# main.net
KiCad netlist of a schematic drawn in EAGLE
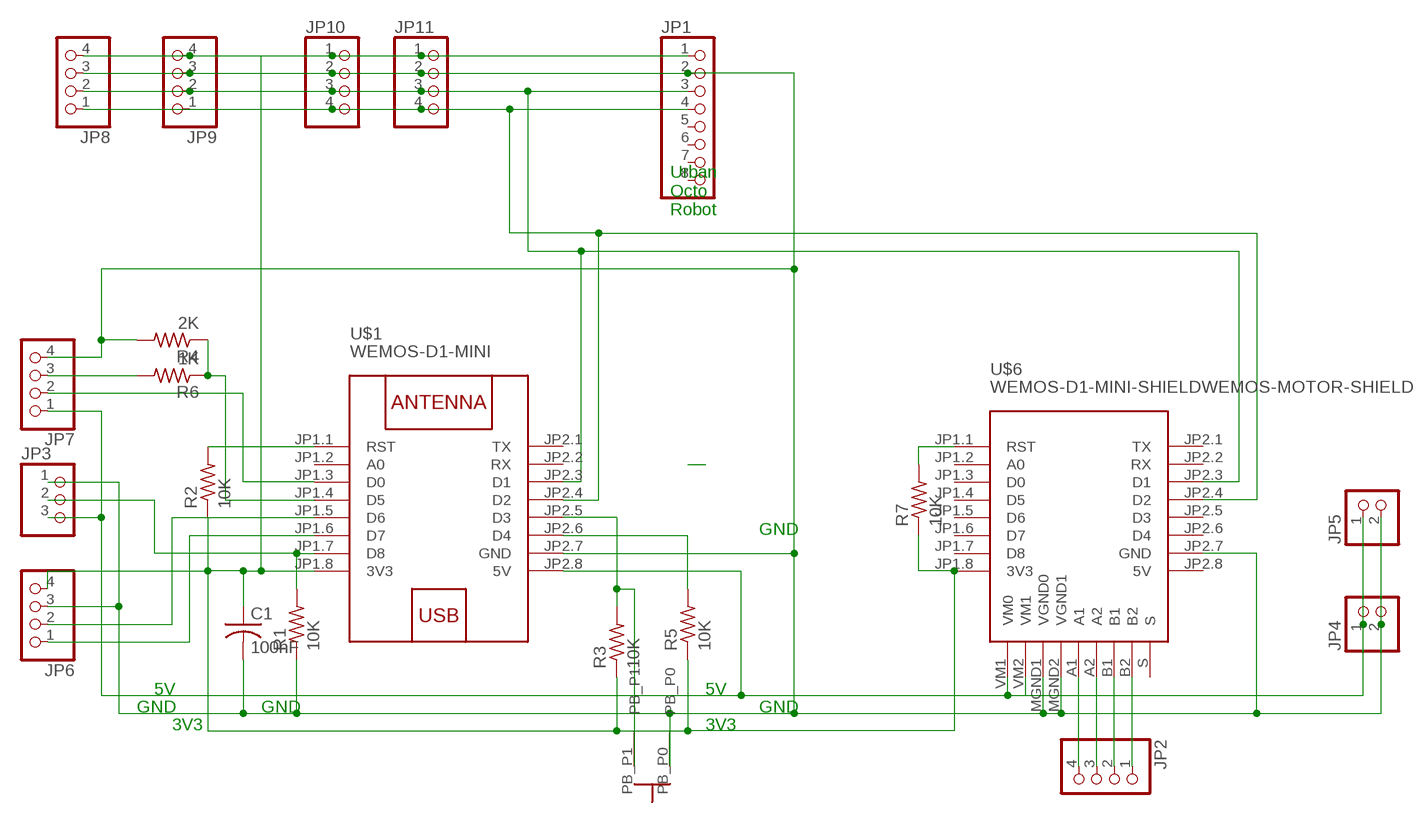
[diagram p0: schematic, sheet 1]

(export (version "E")
  (design (tool "Eeschema 10.0.6"))
  (components
    (comp (ref "C1")
      (value "100nF")
      (footprint "eagle-import:C050-024X044")
      (libsource (lib "eagle-import") (part "C-US050-024X044"))
    )
    (comp (ref "JP1")
      (value "PINHD-1X8")
      (footprint "eagle-import:1X08")
      (libsource (lib "eagle-import") (part "PINHD-1X8"))
    )
    (comp (ref "JP2")
      (value "PINHD-1X4/90")
      (footprint "eagle-import:1X04_90")
      (libsource (lib "eagle-import") (part "PINHD-1X4/90"))
    )
    (comp (ref "JP3")
      (value "PINHD-1X3")
      (footprint "eagle-import:1X03")
      (libsource (lib "eagle-import") (part "PINHD-1X3"))
    )
    (comp (ref "JP4")
      (value "PINHD-1X2")
      (footprint "eagle-import:1X02")
      (libsource (lib "eagle-import") (part "PINHD-1X2"))
    )
    (comp (ref "JP5")
      (value "PINHD-1X2")
      (footprint "eagle-import:1X02")
      (libsource (lib "eagle-import") (part "PINHD-1X2"))
    )
    (comp (ref "JP6")
      (value "PINHD-1X4")
      (footprint "eagle-import:1X04")
      (libsource (lib "eagle-import") (part "PINHD-1X4"))
    )
    (comp (ref "JP7")
      (value "PINHD-1X4")
      (footprint "eagle-import:1X04")
      (libsource (lib "eagle-import") (part "PINHD-1X4"))
    )
    (comp (ref "JP8")
      (value "PINHD-1X4")
      (footprint "eagle-import:1X04")
      (libsource (lib "eagle-import") (part "PINHD-1X4"))
    )
    (comp (ref "JP9")
      (value "PINHD-1X4")
      (footprint "eagle-import:1X04")
      (libsource (lib "eagle-import") (part "PINHD-1X4"))
    )
    (comp (ref "JP10")
      (value "PINHD-1X4")
      (footprint "eagle-import:1X04")
      (libsource (lib "eagle-import") (part "PINHD-1X4"))
    )
    (comp (ref "JP11")
      (value "PINHD-1X4")
      (footprint "eagle-import:1X04")
      (libsource (lib "eagle-import") (part "PINHD-1X4"))
    )
    (comp (ref "R1")
      (value "10K")
      (footprint "eagle-import:0204_7")
      (libsource (lib "eagle-import") (part "R-US_0204/7"))
    )
    (comp (ref "R2")
      (value "10K")
      (footprint "eagle-import:0204_7")
      (libsource (lib "eagle-import") (part "R-US_0204/7"))
    )
    (comp (ref "R3")
      (value "10K")
      (footprint "eagle-import:0204_7")
      (libsource (lib "eagle-import") (part "R-US_0204/7"))
    )
    (comp (ref "R4")
      (value "2K")
      (footprint "eagle-import:0309V")
      (libsource (lib "eagle-import") (part "R-US_0309/V"))
    )
    (comp (ref "R5")
      (value "10K")
      (footprint "eagle-import:0204_7")
      (libsource (lib "eagle-import") (part "R-US_0204/7"))
    )
    (comp (ref "R6")
      (value "1K")
      (footprint "eagle-import:0309V")
      (libsource (lib "eagle-import") (part "R-US_0309/V"))
    )
    (comp (ref "R7")
      (value "10K")
      (footprint "eagle-import:0204_7")
      (libsource (lib "eagle-import") (part "R-US_0204/7"))
    )
    (comp (ref "U$1")
      (value "WEMOS-D1-MINI")
      (footprint "eagle-import:WEMOS-D1-MINI")
      (libsource (lib "eagle-import") (part "WEMOS-D1-MINI"))
    )
    (comp (ref "U$6")
      (value "WEMOS-D1-MINI-SHIELDWEMOS-MOTOR-SHIELD")
      (footprint "eagle-import:WEMOS-D1-MINI-SHIELD")
      (libsource (lib "eagle-import") (part "WEMOS-D1-MINI-SHIELDWEMOS-MOTOR-SHIELD"))
    )
    (comp (ref "U$7")
      (value "BUTTON6X6X10MMSIDE")
      (footprint "eagle-import:BUTTON6X6X10MMSIDE")
      (libsource (lib "eagle-import") (part "BUTTON6X6X10MMSIDE"))
    )
  )
  (nets
    (net (code "1") (name "/5V") (class "Default")
      (node (ref "U$6") (pin "JP2.8") (pinfunction "5V_JP2.8") (pintype "power_in"))
    )
    (net (code "2") (name "Net-(JP2-Pad1)") (class "Default")
      (node (ref "JP2") (pin "1") (pinfunction "1_1") (pintype "passive"))
      (node (ref "U$6") (pin "B2") (pinfunction "B2_B2") (pintype "bidirectional"))
    )
    (net (code "3") (name "Net-(JP2-Pad2)") (class "Default")
      (node (ref "JP2") (pin "2") (pinfunction "2_2") (pintype "passive"))
      (node (ref "U$6") (pin "B1") (pinfunction "B1_B1") (pintype "bidirectional"))
    )
    (net (code "4") (name "Net-(JP2-Pad3)") (class "Default")
      (node (ref "JP2") (pin "3") (pinfunction "3_3") (pintype "passive"))
      (node (ref "U$6") (pin "A2") (pinfunction "A2_A2") (pintype "bidirectional"))
    )
    (net (code "5") (name "Net-(JP2-Pad4)") (class "Default")
      (node (ref "JP2") (pin "4") (pinfunction "4_4") (pintype "passive"))
      (node (ref "U$6") (pin "A1") (pinfunction "A1_A1") (pintype "bidirectional"))
    )
    (net (code "6") (name "Net-(JP7-Pad3)") (class "Default")
      (node (ref "JP7") (pin "3") (pinfunction "3_3") (pintype "passive"))
      (node (ref "R6") (pin "2") (pinfunction "2_2") (pintype "passive"))
    )
    (net (code "7") (name "Net-(U$1-3V3)") (class "Default")
      (node (ref "C1") (pin "1") (pinfunction "1_1") (pintype "passive"))
      (node (ref "JP1") (pin "1") (pinfunction "1_1") (pintype "passive"))
      (node (ref "JP10") (pin "1") (pinfunction "1_1") (pintype "passive"))
      (node (ref "JP11") (pin "1") (pinfunction "1_1") (pintype "passive"))
      (node (ref "JP6") (pin "4") (pinfunction "4_4") (pintype "passive"))
      (node (ref "JP8") (pin "4") (pinfunction "4_4") (pintype "passive"))
      (node (ref "JP9") (pin "4") (pinfunction "4_4") (pintype "passive"))
      (node (ref "R2") (pin "1") (pinfunction "1_1") (pintype "passive"))
      (node (ref "R3") (pin "1") (pinfunction "1_1") (pintype "passive"))
      (node (ref "R5") (pin "1") (pinfunction "1_1") (pintype "passive"))
      (node (ref "R7") (pin "1") (pinfunction "1_1") (pintype "passive"))
      (node (ref "U$1") (pin "JP1.8") (pinfunction "3V3_JP1.8") (pintype "power_in"))
      (node (ref "U$6") (pin "JP1.8") (pinfunction "3V3_JP1.8") (pintype "power_in"))
    )
    (net (code "8") (name "Net-(U$1-5V)") (class "Default")
      (node (ref "JP3") (pin "3") (pinfunction "3_3") (pintype "passive"))
      (node (ref "JP4") (pin "1") (pinfunction "1_1") (pintype "passive"))
      (node (ref "JP5") (pin "1") (pinfunction "1_1") (pintype "passive"))
      (node (ref "JP7") (pin "1") (pinfunction "1_1") (pintype "passive"))
      (node (ref "U$1") (pin "JP2.8") (pinfunction "5V_JP2.8") (pintype "power_in"))
      (node (ref "U$6") (pin "VM1") (pinfunction "VM0_VM1") (pintype "bidirectional"))
      (node (ref "U$6") (pin "VM2") (pinfunction "VM1_VM2") (pintype "bidirectional"))
    )
    (net (code "9") (name "Net-(U$1-D0)") (class "Default")
      (node (ref "JP7") (pin "2") (pinfunction "2_2") (pintype "passive"))
      (node (ref "U$1") (pin "JP1.3") (pinfunction "D0_JP1.3") (pintype "bidirectional"))
    )
    (net (code "10") (name "Net-(U$1-D1)") (class "Default")
      (node (ref "JP1") (pin "3") (pinfunction "3_3") (pintype "passive"))
      (node (ref "JP10") (pin "3") (pinfunction "3_3") (pintype "passive"))
      (node (ref "JP11") (pin "3") (pinfunction "3_3") (pintype "passive"))
      (node (ref "JP8") (pin "2") (pinfunction "2_2") (pintype "passive"))
      (node (ref "JP9") (pin "2") (pinfunction "2_2") (pintype "passive"))
      (node (ref "U$1") (pin "JP2.3") (pinfunction "D1_JP2.3") (pintype "bidirectional"))
      (node (ref "U$6") (pin "JP2.3") (pinfunction "D1_JP2.3") (pintype "bidirectional"))
    )
    (net (code "11") (name "Net-(U$1-D2)") (class "Default")
      (node (ref "JP1") (pin "4") (pinfunction "4_4") (pintype "passive"))
      (node (ref "JP10") (pin "4") (pinfunction "4_4") (pintype "passive"))
      (node (ref "JP11") (pin "4") (pinfunction "4_4") (pintype "passive"))
      (node (ref "JP8") (pin "1") (pinfunction "1_1") (pintype "passive"))
      (node (ref "JP9") (pin "1") (pinfunction "1_1") (pintype "passive"))
      (node (ref "U$1") (pin "JP2.4") (pinfunction "D2_JP2.4") (pintype "bidirectional"))
      (node (ref "U$6") (pin "JP2.4") (pinfunction "D2_JP2.4") (pintype "bidirectional"))
    )
    (net (code "12") (name "Net-(U$1-D3)") (class "Default")
      (node (ref "R3") (pin "2") (pinfunction "2_2") (pintype "passive"))
      (node (ref "U$1") (pin "JP2.5") (pinfunction "D3_JP2.5") (pintype "bidirectional"))
      (node (ref "U$7") (pin "PB_P1") (pinfunction "PB_P1_PB_P1") (pintype "bidirectional"))
    )
    (net (code "13") (name "Net-(U$1-D4)") (class "Default")
      (node (ref "R5") (pin "2") (pinfunction "2_2") (pintype "passive"))
      (node (ref "U$1") (pin "JP2.6") (pinfunction "D4_JP2.6") (pintype "bidirectional"))
    )
    (net (code "14") (name "Net-(U$1-D5)") (class "Default")
      (node (ref "R4") (pin "1") (pinfunction "1_1") (pintype "passive"))
      (node (ref "R6") (pin "1") (pinfunction "1_1") (pintype "passive"))
      (node (ref "U$1") (pin "JP1.4") (pinfunction "D5_JP1.4") (pintype "bidirectional"))
    )
    (net (code "15") (name "Net-(U$1-D6)") (class "Default")
      (node (ref "JP6") (pin "2") (pinfunction "2_2") (pintype "passive"))
      (node (ref "U$1") (pin "JP1.5") (pinfunction "D6_JP1.5") (pintype "bidirectional"))
    )
    (net (code "16") (name "Net-(U$1-D7)") (class "Default")
      (node (ref "JP6") (pin "1") (pinfunction "1_1") (pintype "passive"))
      (node (ref "U$1") (pin "JP1.6") (pinfunction "D7_JP1.6") (pintype "bidirectional"))
    )
    (net (code "17") (name "Net-(U$1-D8)") (class "Default")
      (node (ref "JP3") (pin "2") (pinfunction "2_2") (pintype "passive"))
      (node (ref "R1") (pin "2") (pinfunction "2_2") (pintype "passive"))
      (node (ref "U$1") (pin "JP1.7") (pinfunction "D8_JP1.7") (pintype "bidirectional"))
    )
    (net (code "18") (name "Net-(U$1-GND)") (class "Default")
      (node (ref "C1") (pin "2") (pinfunction "2_2") (pintype "passive"))
      (node (ref "JP1") (pin "2") (pinfunction "2_2") (pintype "passive"))
      (node (ref "JP10") (pin "2") (pinfunction "2_2") (pintype "passive"))
      (node (ref "JP11") (pin "2") (pinfunction "2_2") (pintype "passive"))
      (node (ref "JP3") (pin "1") (pinfunction "1_1") (pintype "passive"))
      (node (ref "JP4") (pin "2") (pinfunction "2_2") (pintype "passive"))
      (node (ref "JP5") (pin "2") (pinfunction "2_2") (pintype "passive"))
      (node (ref "JP6") (pin "3") (pinfunction "3_3") (pintype "passive"))
      (node (ref "JP7") (pin "4") (pinfunction "4_4") (pintype "passive"))
      (node (ref "JP8") (pin "3") (pinfunction "3_3") (pintype "passive"))
      (node (ref "JP9") (pin "3") (pinfunction "3_3") (pintype "passive"))
      (node (ref "R1") (pin "1") (pinfunction "1_1") (pintype "passive"))
      (node (ref "R4") (pin "2") (pinfunction "2_2") (pintype "passive"))
      (node (ref "U$1") (pin "JP2.7") (pinfunction "GND_JP2.7") (pintype "power_in"))
      (node (ref "U$6") (pin "JP2.7") (pinfunction "GND_JP2.7") (pintype "power_in"))
      (node (ref "U$6") (pin "MGND1") (pinfunction "VGND0_MGND1") (pintype "bidirectional"))
      (node (ref "U$6") (pin "MGND2") (pinfunction "VGND1_MGND2") (pintype "bidirectional"))
      (node (ref "U$7") (pin "PB_P0") (pinfunction "PB_P0_PB_P0") (pintype "bidirectional"))
    )
    (net (code "19") (name "Net-(U$1-RST)") (class "Default")
      (node (ref "R2") (pin "2") (pinfunction "2_2") (pintype "passive"))
      (node (ref "U$1") (pin "JP1.1") (pinfunction "RST_JP1.1") (pintype "bidirectional"))
    )
    (net (code "20") (name "Net-(U$6-RST)") (class "Default")
      (node (ref "R7") (pin "2") (pinfunction "2_2") (pintype "passive"))
      (node (ref "U$6") (pin "JP1.1") (pinfunction "RST_JP1.1") (pintype "bidirectional"))
    )
    (net (code "21") (name "unconnected-(JP1-Pad5)") (class "Default")
      (node (ref "JP1") (pin "5") (pinfunction "5_5") (pintype "passive"))
    )
    (net (code "22") (name "unconnected-(JP1-Pad6)") (class "Default")
      (node (ref "JP1") (pin "6") (pinfunction "6_6") (pintype "passive"))
    )
    (net (code "23") (name "unconnected-(JP1-Pad7)") (class "Default")
      (node (ref "JP1") (pin "7") (pinfunction "7_7") (pintype "passive"))
    )
    (net (code "24") (name "unconnected-(JP1-Pad8)") (class "Default")
      (node (ref "JP1") (pin "8") (pinfunction "8_8") (pintype "passive"))
    )
    (net (code "25") (name "unconnected-(U$1-A0-PadJP1.2)") (class "Default")
      (node (ref "U$1") (pin "JP1.2") (pinfunction "A0_JP1.2") (pintype "bidirectional"))
    )
    (net (code "26") (name "unconnected-(U$1-RX-PadJP2.2)") (class "Default")
      (node (ref "U$1") (pin "JP2.2") (pinfunction "RX_JP2.2") (pintype "bidirectional"))
    )
    (net (code "27") (name "unconnected-(U$1-TX-PadJP2.1)") (class "Default")
      (node (ref "U$1") (pin "JP2.1") (pinfunction "TX_JP2.1") (pintype "bidirectional"))
    )
    (net (code "28") (name "unconnected-(U$6-A0-PadJP1.2)") (class "Default")
      (node (ref "U$6") (pin "JP1.2") (pinfunction "A0_JP1.2") (pintype "bidirectional"))
    )
    (net (code "29") (name "unconnected-(U$6-D0-PadJP1.3)") (class "Default")
      (node (ref "U$6") (pin "JP1.3") (pinfunction "D0_JP1.3") (pintype "bidirectional"))
    )
    (net (code "30") (name "unconnected-(U$6-D3-PadJP2.5)") (class "Default")
      (node (ref "U$6") (pin "JP2.5") (pinfunction "D3_JP2.5") (pintype "bidirectional"))
    )
    (net (code "31") (name "unconnected-(U$6-D4-PadJP2.6)") (class "Default")
      (node (ref "U$6") (pin "JP2.6") (pinfunction "D4_JP2.6") (pintype "bidirectional"))
    )
    (net (code "32") (name "unconnected-(U$6-D5-PadJP1.4)") (class "Default")
      (node (ref "U$6") (pin "JP1.4") (pinfunction "D5_JP1.4") (pintype "bidirectional"))
    )
    (net (code "33") (name "unconnected-(U$6-D6-PadJP1.5)") (class "Default")
      (node (ref "U$6") (pin "JP1.5") (pinfunction "D6_JP1.5") (pintype "bidirectional"))
    )
    (net (code "34") (name "unconnected-(U$6-D7-PadJP1.6)") (class "Default")
      (node (ref "U$6") (pin "JP1.6") (pinfunction "D7_JP1.6") (pintype "bidirectional"))
    )
    (net (code "35") (name "unconnected-(U$6-D8-PadJP1.7)") (class "Default")
      (node (ref "U$6") (pin "JP1.7") (pinfunction "D8_JP1.7") (pintype "bidirectional"))
    )
    (net (code "36") (name "unconnected-(U$6-PadS)") (class "Default")
      (node (ref "U$6") (pin "S") (pinfunction "S_S") (pintype "bidirectional"))
    )
    (net (code "37") (name "unconnected-(U$6-RX-PadJP2.2)") (class "Default")
      (node (ref "U$6") (pin "JP2.2") (pinfunction "RX_JP2.2") (pintype "bidirectional"))
    )
    (net (code "38") (name "unconnected-(U$6-TX-PadJP2.1)") (class "Default")
      (node (ref "U$6") (pin "JP2.1") (pinfunction "TX_JP2.1") (pintype "bidirectional"))
    )
  )
)
